# Qwiic_BMI270.net
KiCad netlist of a schematic drawn in EAGLE
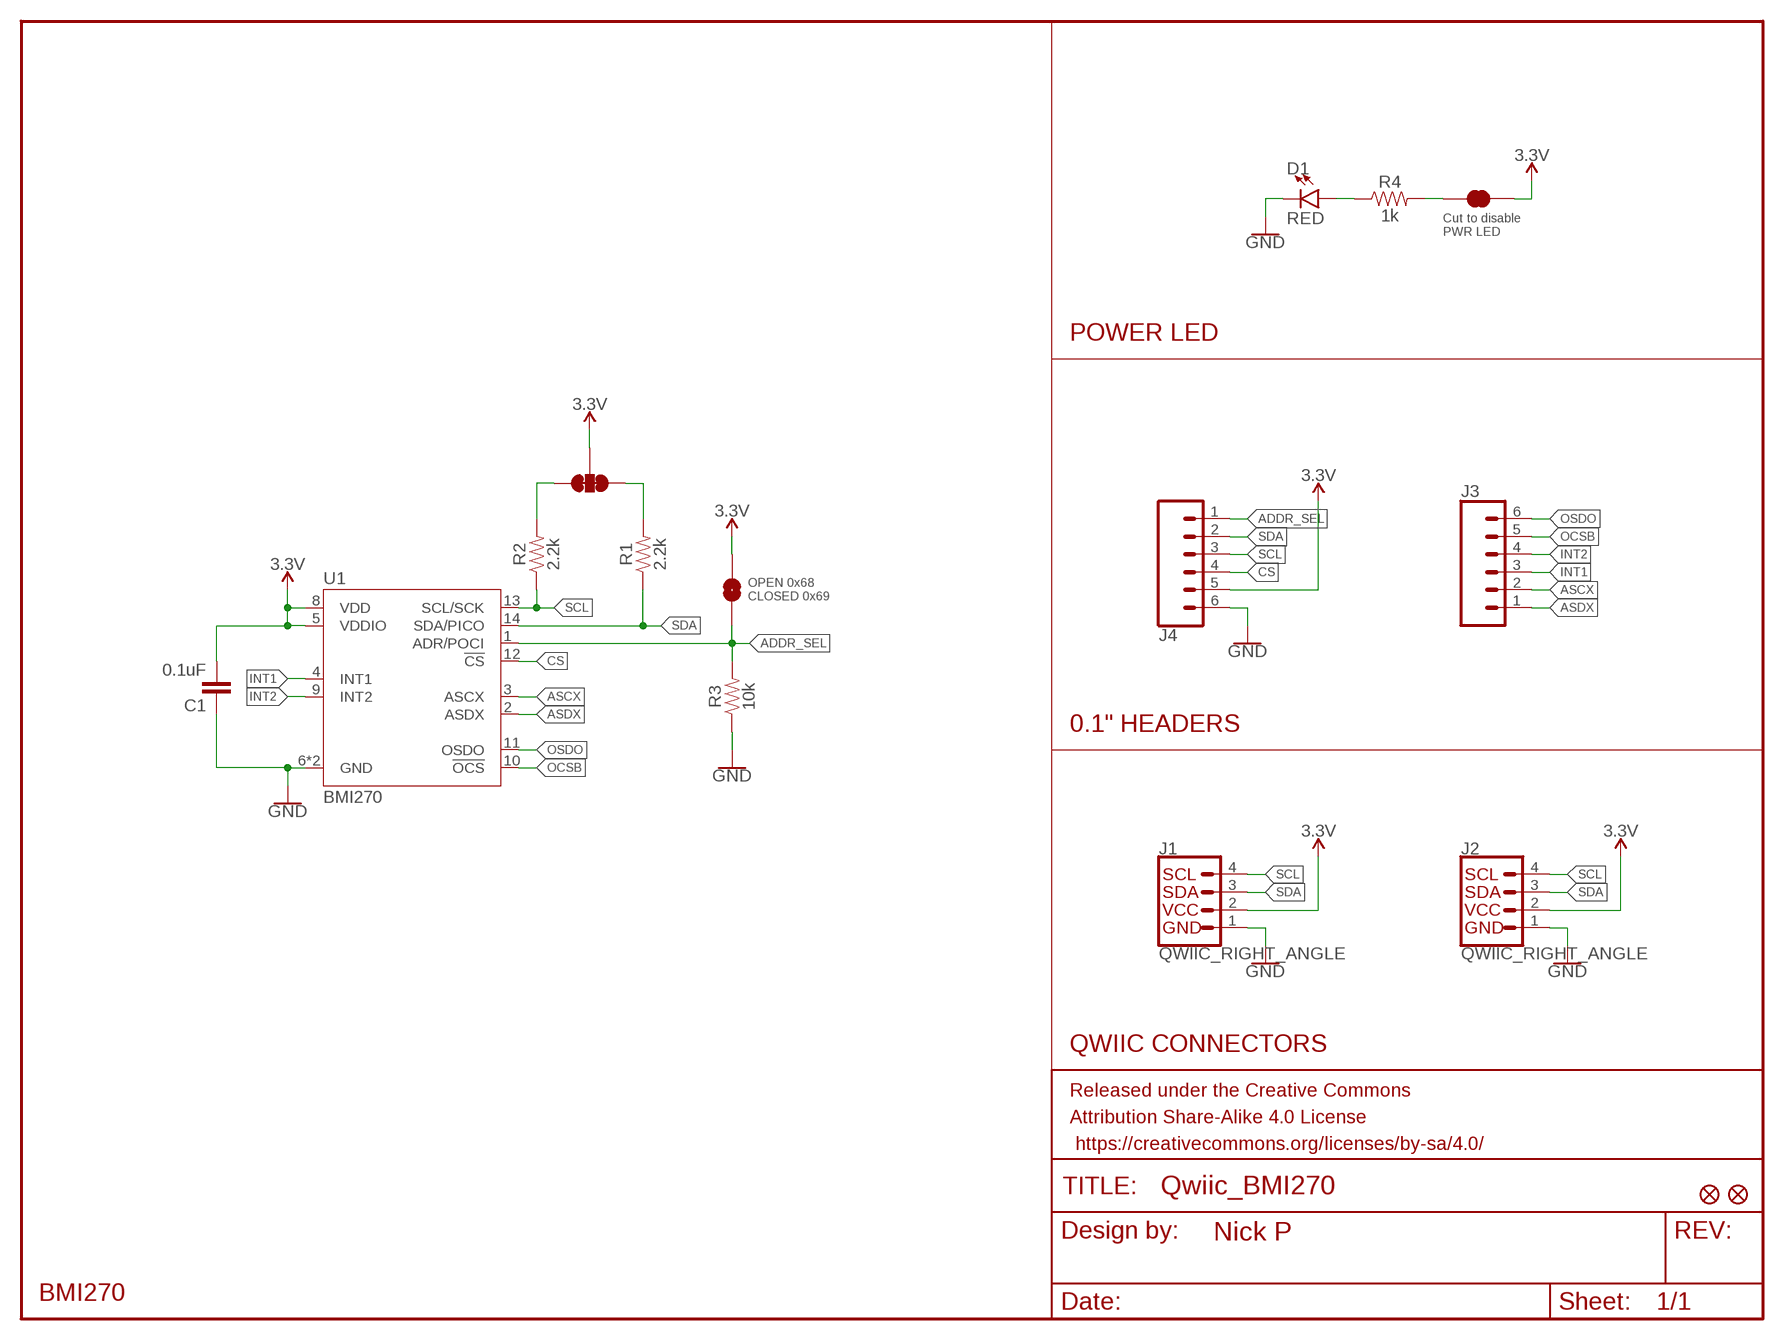
[diagram p0: schematic, sheet 1]

(export (version "E")
  (design (tool "Eeschema 10.0.6"))
  (components
    (comp (ref "C1")
      (value "0.1uF")
      (footprint "eagle-import:0603")
      (libsource (lib "eagle-import") (part "0.1UF-0603-25V-(+80/-20%)"))
    )
    (comp (ref "D1")
      (value "RED")
      (footprint "eagle-import:LED-0603")
      (libsource (lib "eagle-import") (part "LED-RED0603"))
    )
    (comp (ref "FD1")
      (value "FIDUCIAL1X2")
      (footprint "eagle-import:FIDUCIAL-1X2")
      (libsource (lib "eagle-import") (part "FIDUCIAL1X2"))
    )
    (comp (ref "FD2")
      (value "FIDUCIAL1X2")
      (footprint "eagle-import:FIDUCIAL-1X2")
      (libsource (lib "eagle-import") (part "FIDUCIAL1X2"))
    )
    (comp (ref "FRAME1")
      (value "FRAME-LETTERNO_PACKAGE")
      (footprint "eagle-import:DUMMY")
      (fields
        (field (name "DESIGNER") "Nobody")
        (field (name "DESIGNER_1") "Nick P")
        (field (name "VERSION") "x01")
      )
      (libsource (lib "eagle-import") (part "FRAME-LETTERNO_PACKAGE"))
    )
    (comp (ref "J1")
      (value "QWIIC_RIGHT_ANGLE")
      (footprint "eagle-import:JST04_1MM_RA")
      (libsource (lib "eagle-import") (part "QWIIC_CONNECTORJS-1MM"))
    )
    (comp (ref "J2")
      (value "QWIIC_RIGHT_ANGLE")
      (footprint "eagle-import:JST04_1MM_RA")
      (libsource (lib "eagle-import") (part "QWIIC_CONNECTORJS-1MM"))
    )
    (comp (ref "J3")
      (value "CONN_06NO_SILK_FEMALE_PTH")
      (footprint "eagle-import:1X06_NO_SILK")
      (libsource (lib "eagle-import") (part "CONN_06NO_SILK_FEMALE_PTH"))
    )
    (comp (ref "J4")
      (value "CONN_06NO_SILK_FEMALE_PTH")
      (footprint "eagle-import:1X06_NO_SILK")
      (libsource (lib "eagle-import") (part "CONN_06NO_SILK_FEMALE_PTH"))
    )
    (comp (ref "JP1")
      (value "JUMPER-SMT_3_2-NC_TRACE_SILK")
      (footprint "eagle-import:SMT-JUMPER_3_2-NC_TRACE_SILK")
      (libsource (lib "eagle-import") (part "JUMPER-SMT_3_2-NC_TRACE_SILK"))
    )
    (comp (ref "JP2")
      (value "JUMPER-SMT_2_NO_SILK")
      (footprint "eagle-import:SMT-JUMPER_2_NO_SILK")
      (libsource (lib "eagle-import") (part "JUMPER-SMT_2_NO_SILK"))
    )
    (comp (ref "JP3")
      (value "JUMPER-SMT_2_NC_TRACE_SILK")
      (footprint "eagle-import:SMT-JUMPER_2_NC_TRACE_SILK")
      (libsource (lib "eagle-import") (part "JUMPER-SMT_2_NC_TRACE_SILK"))
    )
    (comp (ref "R1")
      (value "2.2k")
      (footprint "eagle-import:0603")
      (libsource (lib "eagle-import") (part "2.2KOHM-0603-1/10W-1%"))
    )
    (comp (ref "R2")
      (value "2.2k")
      (footprint "eagle-import:0603")
      (libsource (lib "eagle-import") (part "2.2KOHM-0603-1/10W-1%"))
    )
    (comp (ref "R3")
      (value "10k")
      (footprint "eagle-import:0603")
      (libsource (lib "eagle-import") (part "10KOHM-0603-1/10W-1%"))
    )
    (comp (ref "R4")
      (value "1k")
      (footprint "eagle-import:0603")
      (libsource (lib "eagle-import") (part "1KOHM-0603-1/10W-1%"))
    )
    (comp (ref "U1")
      (value "BMI270")
      (footprint "eagle-import:BMI270")
      (libsource (lib "eagle-import") (part "BMI270"))
    )
  )
  (nets
    (net (code "1") (name "3.3V") (class "Default")
      (node (ref "C1") (pin "2") (pinfunction "2_2") (pintype "passive"))
      (node (ref "J1") (pin "2") (pinfunction "2_2") (pintype "power_in"))
      (node (ref "J2") (pin "2") (pinfunction "2_2") (pintype "power_in"))
      (node (ref "J4") (pin "5") (pinfunction "5_5") (pintype "passive"))
      (node (ref "JP1") (pin "2") (pinfunction "2_2") (pintype "passive"))
      (node (ref "JP2") (pin "2") (pinfunction "2_2") (pintype "passive"))
      (node (ref "JP3") (pin "2") (pinfunction "2_2") (pintype "passive"))
      (node (ref "U1") (pin "5") (pinfunction "VDDIO_5") (pintype "bidirectional"))
      (node (ref "U1") (pin "8") (pinfunction "VDD_8") (pintype "bidirectional"))
    )
    (net (code "2") (name "ADDR_SEL") (class "Default")
      (node (ref "J4") (pin "1") (pinfunction "1_1") (pintype "passive"))
      (node (ref "JP2") (pin "1") (pinfunction "1_1") (pintype "passive"))
      (node (ref "R3") (pin "2") (pinfunction "2_2") (pintype "passive"))
      (node (ref "U1") (pin "1") (pinfunction "ADR/POCI_1") (pintype "bidirectional"))
    )
    (net (code "3") (name "ASCX") (class "Default")
      (node (ref "J3") (pin "2") (pinfunction "2_2") (pintype "passive"))
      (node (ref "U1") (pin "3") (pinfunction "ASCX_3") (pintype "bidirectional"))
    )
    (net (code "4") (name "ASDX") (class "Default")
      (node (ref "J3") (pin "1") (pinfunction "1_1") (pintype "passive"))
      (node (ref "U1") (pin "2") (pinfunction "ASDX_2") (pintype "bidirectional"))
    )
    (net (code "5") (name "CS") (class "Default")
      (node (ref "J4") (pin "4") (pinfunction "4_4") (pintype "passive"))
      (node (ref "U1") (pin "12") (pinfunction "~{CS}_12") (pintype "bidirectional"))
    )
    (net (code "6") (name "GND") (class "Default")
      (node (ref "C1") (pin "1") (pinfunction "1_1") (pintype "passive"))
      (node (ref "D1") (pin "C") (pinfunction "C_C") (pintype "passive"))
      (node (ref "J1") (pin "1") (pinfunction "1_1") (pintype "power_in"))
      (node (ref "J2") (pin "1") (pinfunction "1_1") (pintype "power_in"))
      (node (ref "J4") (pin "6") (pinfunction "6_6") (pintype "passive"))
      (node (ref "R3") (pin "1") (pinfunction "1_1") (pintype "passive"))
      (node (ref "U1") (pin "6") (pinfunction "GND_6") (pintype "bidirectional"))
      (node (ref "U1") (pin "7") (pinfunction "GND_7") (pintype "bidirectional"))
    )
    (net (code "7") (name "INT1") (class "Default")
      (node (ref "J3") (pin "3") (pinfunction "3_3") (pintype "passive"))
      (node (ref "U1") (pin "4") (pinfunction "INT1_4") (pintype "bidirectional"))
    )
    (net (code "8") (name "INT2") (class "Default")
      (node (ref "J3") (pin "4") (pinfunction "4_4") (pintype "passive"))
      (node (ref "U1") (pin "9") (pinfunction "INT2_9") (pintype "bidirectional"))
    )
    (net (code "9") (name "Net-(D1-PadA)") (class "Default")
      (node (ref "D1") (pin "A") (pinfunction "A_A") (pintype "passive"))
      (node (ref "R4") (pin "1") (pinfunction "1_1") (pintype "passive"))
    )
    (net (code "10") (name "Net-(JP1-Pad1)") (class "Default")
      (node (ref "JP1") (pin "1") (pinfunction "1_1") (pintype "passive"))
      (node (ref "R1") (pin "2") (pinfunction "2_2") (pintype "passive"))
    )
    (net (code "11") (name "Net-(JP1-Pad3)") (class "Default")
      (node (ref "JP1") (pin "3") (pinfunction "3_3") (pintype "passive"))
      (node (ref "R2") (pin "2") (pinfunction "2_2") (pintype "passive"))
    )
    (net (code "12") (name "Net-(JP3-Pad1)") (class "Default")
      (node (ref "JP3") (pin "1") (pinfunction "1_1") (pintype "passive"))
      (node (ref "R4") (pin "2") (pinfunction "2_2") (pintype "passive"))
    )
    (net (code "13") (name "OCSB") (class "Default")
      (node (ref "J3") (pin "5") (pinfunction "5_5") (pintype "passive"))
      (node (ref "U1") (pin "10") (pinfunction "~{OCS}_10") (pintype "bidirectional"))
    )
    (net (code "14") (name "OSDO") (class "Default")
      (node (ref "J3") (pin "6") (pinfunction "6_6") (pintype "passive"))
      (node (ref "U1") (pin "11") (pinfunction "OSDO_11") (pintype "bidirectional"))
    )
    (net (code "15") (name "SCL") (class "Default")
      (node (ref "J1") (pin "4") (pinfunction "4_4") (pintype "passive"))
      (node (ref "J2") (pin "4") (pinfunction "4_4") (pintype "passive"))
      (node (ref "J4") (pin "3") (pinfunction "3_3") (pintype "passive"))
      (node (ref "R2") (pin "1") (pinfunction "1_1") (pintype "passive"))
      (node (ref "U1") (pin "13") (pinfunction "SCL/SCK_13") (pintype "bidirectional"))
    )
    (net (code "16") (name "SDA") (class "Default")
      (node (ref "J1") (pin "3") (pinfunction "3_3") (pintype "passive"))
      (node (ref "J2") (pin "3") (pinfunction "3_3") (pintype "passive"))
      (node (ref "J4") (pin "2") (pinfunction "2_2") (pintype "passive"))
      (node (ref "R1") (pin "1") (pinfunction "1_1") (pintype "passive"))
      (node (ref "U1") (pin "14") (pinfunction "SDA/PICO_14") (pintype "bidirectional"))
    )
  )
)
